# Battery_indicator.net
KiCad netlist of a schematic drawn in Altium Designer
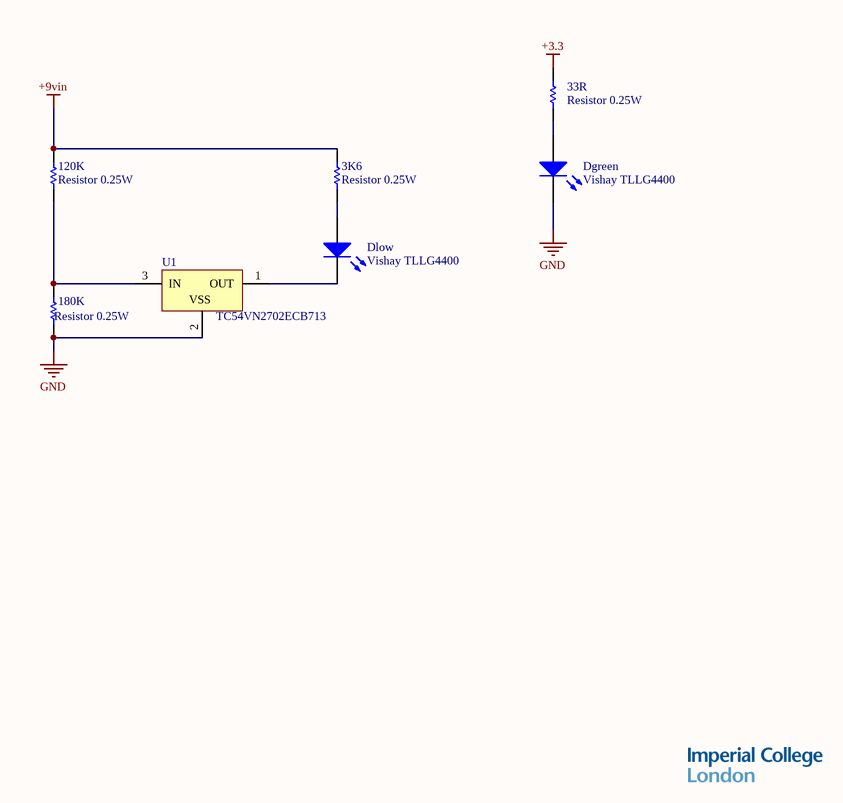
[diagram p0: Battery indicator.SchDoc]

(export (version "E")
  (design (tool "Eeschema 10.0.6"))
  (components
    (comp (ref "3K6")
      (value "Resistor 0.25W")
      (footprint "PCB-3613466-1")
      (libsource (lib "FavoritesLibrary") (part "SYM-b15c796618a36e9b-1"))
    )
    (comp (ref "33R")
      (value "Resistor 0.25W")
      (footprint "PCB-3613466-1")
      (libsource (lib "FavoritesLibrary") (part "SYM-b15c796618a36e9b-1"))
    )
    (comp (ref "120K")
      (value "Resistor 0.25W")
      (footprint "PCB-3613466-1")
      (libsource (lib "FavoritesLibrary") (part "SYM-b15c796618a36e9b-1"))
    )
    (comp (ref "180K")
      (value "Resistor 0.25W")
      (footprint "PCB-3613466-1")
      (libsource (lib "FavoritesLibrary") (part "SYM-b15c796618a36e9b-1"))
    )
    (comp (ref "Dgreen")
      (value "Vishay TLLG4400")
      (footprint "PCB-a4kbstwpa15hyka10z5q-1")
      (description "LED; PCB ; Green; 0.63mcd; 3mm; T-1; 7mA; 1.9V; 565nm; 25deg; GaP on GaP; 20V; 20mW; -40")
      (fields (field (name "MANUFACTURER PART NUMBER") "TLLG4400"))
      (libsource (lib "ProjectLibrary") (part "SYM-afe165a651817026-1"))
    )
    (comp (ref "Dlow")
      (value "Vishay TLLG4400")
      (footprint "PCB-a4kbstwpa15hyka10z5q-1")
      (description "LED; PCB ; Green; 0.63mcd; 3mm; T-1; 7mA; 1.9V; 565nm; 25deg; GaP on GaP; 20V; 20mW; -40")
      (fields (field (name "MANUFACTURER PART NUMBER") "TLLG4400"))
      (libsource (lib "CommunityVault") (part "CMP-afe165a651817026-5"))
    )
    (comp (ref "U1")
      (value "TC54VN2702ECB713")
      (footprint "SOT-23A-CB3_L")
      (libsource (lib "CommunityVault") (part "CMP-1440117-2"))
    )
  )
  (nets
    (net (code "1") (name "+3.3") (class "Default")
      (node (ref "33R") (pin "2") (pinfunction "2_2") (pintype "passive"))
    )
    (net (code "2") (name "+9vin") (class "Default")
      (node (ref "120K") (pin "2") (pinfunction "2_2") (pintype "passive"))
      (node (ref "3K6") (pin "2") (pinfunction "2_2") (pintype "passive"))
    )
    (net (code "3") (name "GND") (class "Default")
      (node (ref "180K") (pin "2") (pinfunction "2_2") (pintype "passive"))
      (node (ref "Dgreen") (pin "2") (pinfunction "K_2") (pintype "passive"))
      (node (ref "U1") (pin "2") (pinfunction "VSS_2") (pintype "power_in"))
    )
    (net (code "4") (name "Net-(Dgreen-A)") (class "Default")
      (node (ref "33R") (pin "1") (pinfunction "1_1") (pintype "passive"))
      (node (ref "Dgreen") (pin "1") (pinfunction "A_1") (pintype "passive"))
    )
    (net (code "5") (name "Net-(Dlow-A)") (class "Default")
      (node (ref "3K6") (pin "1") (pinfunction "1_1") (pintype "passive"))
      (node (ref "Dlow") (pin "1") (pinfunction "A_1") (pintype "passive"))
    )
    (net (code "6") (name "Net-(Dlow-K)") (class "Default")
      (node (ref "Dlow") (pin "2") (pinfunction "K_2") (pintype "passive"))
      (node (ref "U1") (pin "1") (pinfunction "OUT_1") (pintype "power_in"))
    )
    (net (code "7") (name "Net-(U1-IN)") (class "Default")
      (node (ref "120K") (pin "1") (pinfunction "1_1") (pintype "passive"))
      (node (ref "180K") (pin "1") (pinfunction "1_1") (pintype "passive"))
      (node (ref "U1") (pin "3") (pinfunction "IN_3") (pintype "power_in"))
    )
  )
)
